# 1_28_LCD.net
KiCad netlist of a schematic drawn in Altium Designer
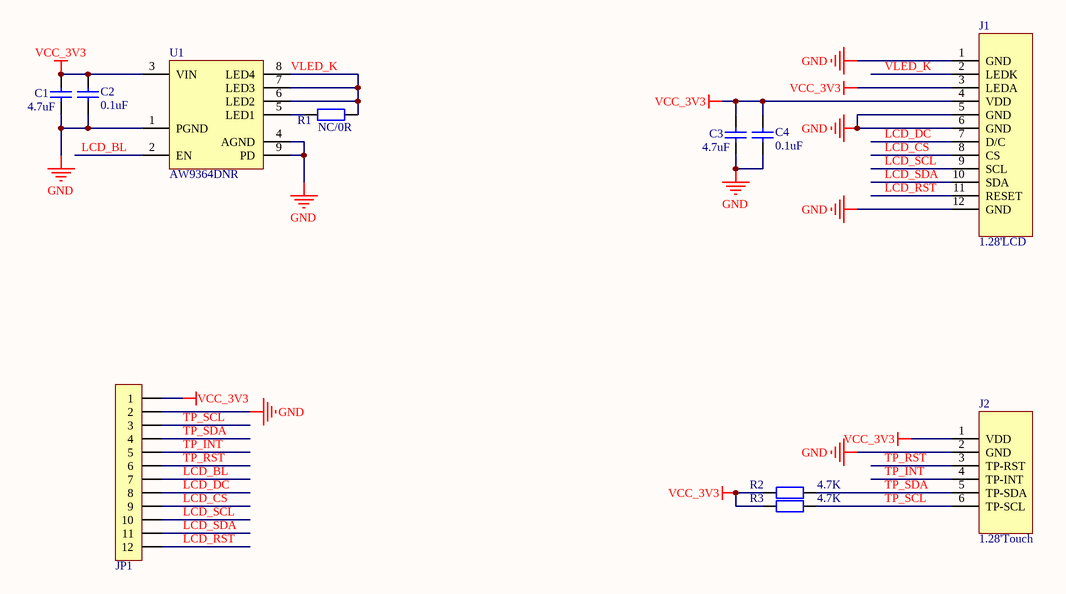
[diagram p0: 1.28'LCD.SchDoc]

(export (version "E")
  (design (tool "Eeschema 10.0.6"))
  (components
    (comp (ref "C1")
      (value "4.7uF")
      (footprint "C0402_L")
      (description "贴片电容")
      (libsource (lib "0.1 - 电阻-电容-电感-晶振-晶体-磁珠-电位器") (part "C"))
    )
    (comp (ref "C2")
      (value "0.1uF")
      (footprint "C0402_L")
      (description "贴片电容")
      (libsource (lib "0.1 - 电阻-电容-电感-晶振-晶体-磁珠-电位器") (part "C"))
    )
    (comp (ref "C3")
      (value "4.7uF")
      (footprint "C0402_L")
      (description "贴片电容")
      (libsource (lib "0.1 - 电阻-电容-电感-晶振-晶体-磁珠-电位器") (part "C"))
    )
    (comp (ref "C4")
      (value "0.1uF")
      (footprint "C0402_L")
      (description "贴片电容")
      (libsource (lib "0.1 - 电阻-电容-电感-晶振-晶体-磁珠-电位器") (part "C"))
    )
    (comp (ref "J1")
      (value "1.28'LCD")
      (footprint "1.28‘LCD")
      (description "1.28寸焊接LCD屏（240*240）")
      (libsource (lib "USER_Lib") (part "1.28'LCD"))
    )
    (comp (ref "J2")
      (value "1.28'Touch")
      (footprint "1.28’Touch")
      (description "1.28寸触摸面板")
      (libsource (lib "USER_Lib") (part "1.28'Touch"))
    )
    (comp (ref "JP1")
      (value "12P-FPC-1.0H")
      (footprint "FPC05-10-12-RL-MA-G")
      (libsource (lib "5.0 - 1.00mm连接器(FPC1.0-SH1.0)") (part "Header 12"))
    )
    (comp (ref "R1")
      (value "NC/0R")
      (footprint "R0402_L")
      (description "贴片电阻")
      (libsource (lib "0.1 - 电阻-电容-电感-晶振-晶体-磁珠-电位器") (part "R"))
    )
    (comp (ref "R2")
      (value "4.7K")
      (footprint "R0402_L")
      (description "贴片电阻")
      (libsource (lib "0.1 - 电阻-电容-电感-晶振-晶体-磁珠-电位器") (part "R"))
    )
    (comp (ref "R3")
      (value "4.7K")
      (footprint "R0402_L")
      (description "贴片电阻")
      (libsource (lib "0.1 - 电阻-电容-电感-晶振-晶体-磁珠-电位器") (part "R"))
    )
    (comp (ref "U1")
      (value "AW9364DNR")
      (footprint "DFN2X2-8L")
      (description "并联调光背光驱动")
      (libsource (lib "USER_Lib") (part "AW9364DNR"))
    )
  )
  (nets
    (net (code "1") (name "/LCD_BL") (class "Default")
      (node (ref "JP1") (pin "7") (pinfunction "7_7") (pintype "passive"))
      (node (ref "U1") (pin "2") (pinfunction "EN_2") (pintype "passive"))
    )
    (net (code "2") (name "/LCD_CS") (class "Default")
      (node (ref "J1") (pin "8") (pinfunction "CS_8") (pintype "passive"))
      (node (ref "JP1") (pin "9") (pinfunction "9_9") (pintype "passive"))
    )
    (net (code "3") (name "/LCD_DC") (class "Default")
      (node (ref "J1") (pin "7") (pinfunction "D/C_7") (pintype "passive"))
      (node (ref "JP1") (pin "8") (pinfunction "8_8") (pintype "passive"))
    )
    (net (code "4") (name "/LCD_RST") (class "Default")
      (node (ref "J1") (pin "11") (pinfunction "RESET_11") (pintype "passive"))
      (node (ref "JP1") (pin "12") (pinfunction "12_12") (pintype "passive"))
    )
    (net (code "5") (name "/LCD_SCL") (class "Default")
      (node (ref "J1") (pin "9") (pinfunction "SCL_9") (pintype "passive"))
      (node (ref "JP1") (pin "10") (pinfunction "10_10") (pintype "passive"))
    )
    (net (code "6") (name "/LCD_SDA") (class "Default")
      (node (ref "J1") (pin "10") (pinfunction "SDA_10") (pintype "passive"))
      (node (ref "JP1") (pin "11") (pinfunction "11_11") (pintype "passive"))
    )
    (net (code "7") (name "/TP_INT") (class "Default")
      (node (ref "J2") (pin "4") (pinfunction "TP-INT_4") (pintype "passive"))
      (node (ref "JP1") (pin "5") (pinfunction "5_5") (pintype "passive"))
    )
    (net (code "8") (name "/TP_RST") (class "Default")
      (node (ref "J2") (pin "3") (pinfunction "TP-RST_3") (pintype "passive"))
      (node (ref "JP1") (pin "6") (pinfunction "6_6") (pintype "passive"))
    )
    (net (code "9") (name "/TP_SCL") (class "Default")
      (node (ref "J2") (pin "6") (pinfunction "TP-SCL_6") (pintype "passive"))
      (node (ref "JP1") (pin "3") (pinfunction "3_3") (pintype "passive"))
      (node (ref "R3") (pin "2") (pinfunction "2_2") (pintype "passive"))
    )
    (net (code "10") (name "/TP_SDA") (class "Default")
      (node (ref "J2") (pin "5") (pinfunction "TP-SDA_5") (pintype "passive"))
      (node (ref "JP1") (pin "4") (pinfunction "4_4") (pintype "passive"))
      (node (ref "R2") (pin "2") (pinfunction "2_2") (pintype "passive"))
    )
    (net (code "11") (name "/VLED_K") (class "Default")
      (node (ref "J1") (pin "2") (pinfunction "LEDK_2") (pintype "passive"))
      (node (ref "R1") (pin "1") (pinfunction "1_1") (pintype "passive"))
      (node (ref "U1") (pin "6") (pinfunction "LED2_6") (pintype "passive"))
      (node (ref "U1") (pin "7") (pinfunction "LED3_7") (pintype "passive"))
      (node (ref "U1") (pin "8") (pinfunction "LED4_8") (pintype "passive"))
    )
    (net (code "12") (name "GND") (class "Default")
      (node (ref "C1") (pin "1") (pinfunction "1_1") (pintype "passive"))
      (node (ref "C2") (pin "1") (pinfunction "1_1") (pintype "passive"))
      (node (ref "C3") (pin "1") (pinfunction "1_1") (pintype "passive"))
      (node (ref "C4") (pin "1") (pinfunction "1_1") (pintype "passive"))
      (node (ref "J1") (pin "1") (pinfunction "GND_1") (pintype "passive"))
      (node (ref "J1") (pin "12") (pinfunction "GND_12") (pintype "passive"))
      (node (ref "J1") (pin "5") (pinfunction "GND_5") (pintype "passive"))
      (node (ref "J1") (pin "6") (pinfunction "GND_6") (pintype "passive"))
      (node (ref "J2") (pin "2") (pinfunction "GND_2") (pintype "passive"))
      (node (ref "JP1") (pin "2") (pinfunction "2_2") (pintype "passive"))
      (node (ref "U1") (pin "1") (pinfunction "PGND_1") (pintype "passive"))
      (node (ref "U1") (pin "4") (pinfunction "AGND_4") (pintype "passive"))
      (node (ref "U1") (pin "9") (pinfunction "PD_9") (pintype "passive"))
    )
    (net (code "13") (name "Net-(U1-LED1)") (class "Default")
      (node (ref "R1") (pin "2") (pinfunction "2_2") (pintype "passive"))
      (node (ref "U1") (pin "5") (pinfunction "LED1_5") (pintype "passive"))
    )
    (net (code "14") (name "VCC_3V3") (class "Default")
      (node (ref "C1") (pin "2") (pinfunction "2_2") (pintype "passive"))
      (node (ref "C2") (pin "2") (pinfunction "2_2") (pintype "passive"))
      (node (ref "C3") (pin "2") (pinfunction "2_2") (pintype "passive"))
      (node (ref "C4") (pin "2") (pinfunction "2_2") (pintype "passive"))
      (node (ref "J1") (pin "3") (pinfunction "LEDA_3") (pintype "passive"))
      (node (ref "J1") (pin "4") (pinfunction "VDD_4") (pintype "passive"))
      (node (ref "J2") (pin "1") (pinfunction "VDD_1") (pintype "passive"))
      (node (ref "JP1") (pin "1") (pinfunction "1_1") (pintype "passive"))
      (node (ref "R2") (pin "1") (pinfunction "1_1") (pintype "passive"))
      (node (ref "R3") (pin "1") (pinfunction "1_1") (pintype "passive"))
      (node (ref "U1") (pin "3") (pinfunction "VIN_3") (pintype "passive"))
    )
  )
)
